# 4_CONN_schdoc.net
KiCad netlist of a schematic drawn in Altium Designer
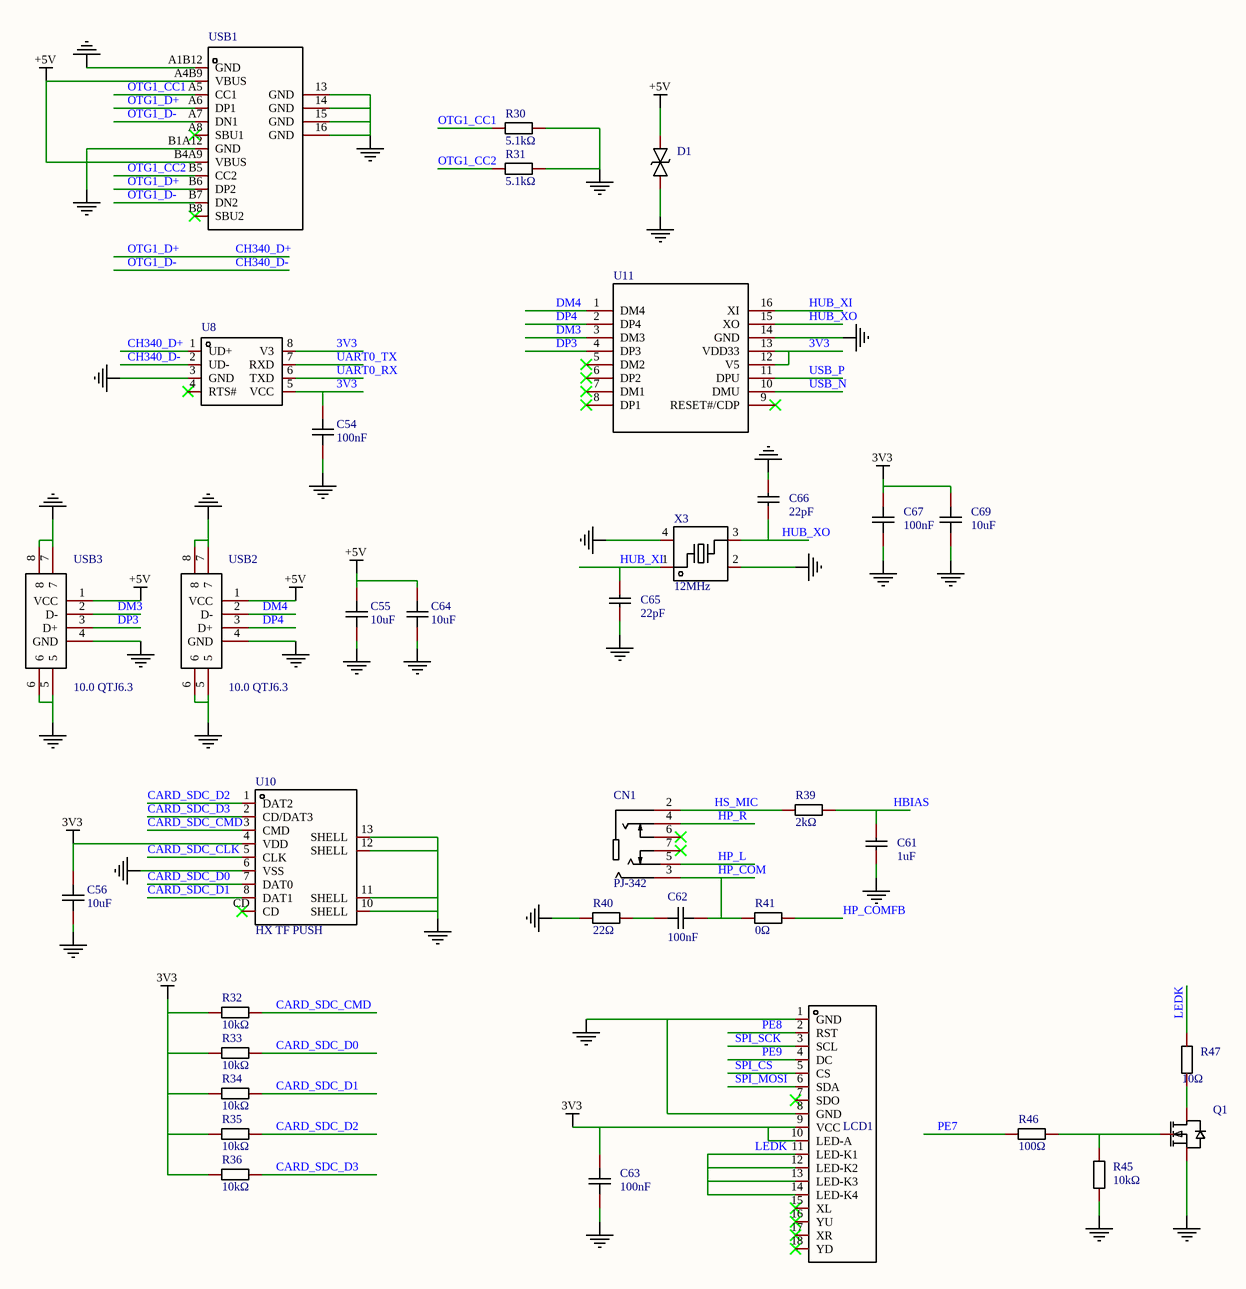
[diagram p0: 4_CONN.schdoc.schdoc]

(export (version "E")
  (design (tool "Eeschema 10.0.6"))
  (components
    (comp (ref "C54")
      (value "100nF")
      (fields
        (field (name "NAME") "100nF")
        (field (name "MANUFACTURER") "YAGEO(国巨)")
        (field (name "MANUFACTURER PART") "CC0603KRX7R9BB104")
        (field (name "TOLERANCE") "±10%")
      )
      (libsource (lib "altium-import") (part "root_1_CC0603KRX7R9BB104_"))
    )
    (comp (ref "C55")
      (value "10uF")
      (fields
        (field (name "NAME") "10uF")
        (field (name "MANUFACTURER") "SAMSUNG(三星)")
        (field (name "MANUFACTURER PART") "CL10A106KP8NNNC")
        (field (name "TOLERANCE") "±10%")
      )
      (libsource (lib "altium-import") (part "root_1_CL10A106KP8NNNC_"))
    )
    (comp (ref "C56")
      (value "10uF")
      (fields
        (field (name "NAME") "10uF")
        (field (name "MANUFACTURER") "SAMSUNG(三星)")
        (field (name "MANUFACTURER PART") "CL10A106KP8NNNC")
        (field (name "TOLERANCE") "±10%")
      )
      (libsource (lib "altium-import") (part "root_1_CL10A106KP8NNNC_"))
    )
    (comp (ref "C61")
      (value "1uF")
      (fields
        (field (name "NAME") "1uF")
        (field (name "MANUFACTURER PART") "CL10A105KB8NNNC")
        (field (name "MANUFACTURER") "SAMSUNG(三星)")
        (field (name "TOLERANCE") "±10%")
      )
      (libsource (lib "altium-import") (part "root_1_CL10A105KB8NNNC_"))
    )
    (comp (ref "C62")
      (value "100nF")
      (fields
        (field (name "NAME") "100nF")
        (field (name "MANUFACTURER") "YAGEO(国巨)")
        (field (name "MANUFACTURER PART") "CC0603KRX7R9BB104")
        (field (name "TOLERANCE") "±10%")
      )
      (libsource (lib "altium-import") (part "root_2_CC0603KRX7R9BB104_"))
    )
    (comp (ref "C63")
      (value "100nF")
      (fields
        (field (name "NAME") "100nF")
        (field (name "MANUFACTURER") "YAGEO(国巨)")
        (field (name "MANUFACTURER PART") "CC0603KRX7R9BB104")
        (field (name "TOLERANCE") "±10%")
      )
      (libsource (lib "altium-import") (part "root_1_CC0603KRX7R9BB104_"))
    )
    (comp (ref "C64")
      (value "10uF")
      (fields
        (field (name "NAME") "10uF")
        (field (name "MANUFACTURER") "SAMSUNG(三星)")
        (field (name "MANUFACTURER PART") "CL10A106KP8NNNC")
        (field (name "TOLERANCE") "±10%")
      )
      (libsource (lib "altium-import") (part "root_1_CL10A106KP8NNNC_"))
    )
    (comp (ref "C65")
      (value "22pF")
      (fields
        (field (name "NAME") "22pF")
        (field (name "MANUFACTURER PART") "CL10C220JB8NNNC")
        (field (name "MANUFACTURER") "SAMSUNG(三星)")
        (field (name "TOLERANCE") "±5%")
      )
      (libsource (lib "altium-import") (part "root_1_CL10C220JB8NNNC_"))
    )
    (comp (ref "C66")
      (value "22pF")
      (fields
        (field (name "NAME") "22pF")
        (field (name "MANUFACTURER PART") "CL10C220JB8NNNC")
        (field (name "MANUFACTURER") "SAMSUNG(三星)")
        (field (name "TOLERANCE") "±5%")
      )
      (libsource (lib "altium-import") (part "root_1_CL10C220JB8NNNC_"))
    )
    (comp (ref "C67")
      (value "100nF")
      (fields
        (field (name "NAME") "100nF")
        (field (name "MANUFACTURER") "YAGEO(国巨)")
        (field (name "MANUFACTURER PART") "CC0603KRX7R9BB104")
        (field (name "TOLERANCE") "±10%")
      )
      (libsource (lib "altium-import") (part "root_1_CC0603KRX7R9BB104_"))
    )
    (comp (ref "C69")
      (value "10uF")
      (fields
        (field (name "NAME") "10uF")
        (field (name "MANUFACTURER") "SAMSUNG(三星)")
        (field (name "MANUFACTURER PART") "CL10A106KP8NNNC")
        (field (name "TOLERANCE") "±10%")
      )
      (libsource (lib "altium-import") (part "root_1_CL10A106KP8NNNC_"))
    )
    (comp (ref "CN1")
      (value "PJ-342")
      (description "连接器类型:3.5mm耳机座;额定电流:500mA;额定电压:30V;工作温度范围:-30℃~+70℃;")
      (fields (field (name "NAME") "PJ-342") (field (name "MANUFACTURER") "SHOU HAN(首韩)"))
      (libsource (lib "altium-import") (part "root_0_PJ-342_C668606_"))
    )
    (comp (ref "D1")
      (value "SMF5.0CA")
      (description "极性:双向;反向截止电压(Vrwm):5V;击穿电压:6.4V;反向漏电流(Ir):800uA;峰值脉冲电流(Ipp)@10/1000μs:21.7A;最大钳位电压:9.2V;")
      (fields (field (name "MANUFACTURER") "AnBon(安邦)"))
      (libsource (lib "altium-import") (part "root_1_SMF5.0CA_C435453_"))
    )
    (comp (ref "LCD1")
      (value "TFT_2.4_18P_SPI_ILI9341_240X320_65K_S_1")
      (description "2.4寸SPI串口液晶屏TFT彩屏ILI9341驱动")
      (libsource (lib "altium-import") (part "root_0_TFT_2.4_18P_SPI_ILI9341_240X320_65K_S_1_"))
    )
    (comp (ref "Q1")
      (value "ao3400_c841146")
      (fields (field (name "MANUFACTURER") "LGE(鲁光)") (field (name "MANUFACTURER PART") "AO3400"))
      (libsource (lib "altium-import") (part "root_0_ao3400_c841146_"))
    )
    (comp (ref "R30")
      (value "5.1kΩ")
      (fields
        (field (name "NAME") "5.1kΩ")
        (field (name "MANUFACTURER") "UNI-ROYAL(厚声)")
        (field (name "MANUFACTURER PART") "0402WGF5101TCE")
        (field (name "TOLERANCE") "±1%")
      )
      (libsource (lib "altium-import") (part "root_0_0402WGF5101TCE_"))
    )
    (comp (ref "R31")
      (value "5.1kΩ")
      (fields
        (field (name "NAME") "5.1kΩ")
        (field (name "MANUFACTURER") "UNI-ROYAL(厚声)")
        (field (name "MANUFACTURER PART") "0402WGF5101TCE")
        (field (name "TOLERANCE") "±1%")
      )
      (libsource (lib "altium-import") (part "root_0_0402WGF5101TCE_"))
    )
    (comp (ref "R32")
      (value "10kΩ")
      (description "电阻类型:厚膜电阻;阻值:10kΩ;精度:±1%;功率:100mW;温度系数:±100ppm/℃;最大工作电压:75V;工作温度范围:-55℃~+155℃;")
      (fields
        (field (name "NAME") "10kΩ")
        (field (name "MANUFACTURER") "UNI-ROYAL(厚声)")
        (field (name "MANUFACTURER PART") "0603WAF1002T5E")
      )
      (libsource (lib "altium-import") (part "root_0_0603WAF1002T5E_"))
    )
    (comp (ref "R33")
      (value "10kΩ")
      (description "电阻类型:厚膜电阻;阻值:10kΩ;精度:±1%;功率:100mW;温度系数:±100ppm/℃;最大工作电压:75V;工作温度范围:-55℃~+155℃;")
      (fields
        (field (name "NAME") "10kΩ")
        (field (name "MANUFACTURER") "UNI-ROYAL(厚声)")
        (field (name "MANUFACTURER PART") "0603WAF1002T5E")
      )
      (libsource (lib "altium-import") (part "root_0_0603WAF1002T5E_"))
    )
    (comp (ref "R34")
      (value "10kΩ")
      (description "电阻类型:厚膜电阻;阻值:10kΩ;精度:±1%;功率:100mW;温度系数:±100ppm/℃;最大工作电压:75V;工作温度范围:-55℃~+155℃;")
      (fields
        (field (name "NAME") "10kΩ")
        (field (name "MANUFACTURER") "UNI-ROYAL(厚声)")
        (field (name "MANUFACTURER PART") "0603WAF1002T5E")
      )
      (libsource (lib "altium-import") (part "root_0_0603WAF1002T5E_"))
    )
    (comp (ref "R35")
      (value "10kΩ")
      (description "电阻类型:厚膜电阻;阻值:10kΩ;精度:±1%;功率:100mW;温度系数:±100ppm/℃;最大工作电压:75V;工作温度范围:-55℃~+155℃;")
      (fields
        (field (name "NAME") "10kΩ")
        (field (name "MANUFACTURER") "UNI-ROYAL(厚声)")
        (field (name "MANUFACTURER PART") "0603WAF1002T5E")
      )
      (libsource (lib "altium-import") (part "root_0_0603WAF1002T5E_"))
    )
    (comp (ref "R36")
      (value "10kΩ")
      (description "电阻类型:厚膜电阻;阻值:10kΩ;精度:±1%;功率:100mW;温度系数:±100ppm/℃;最大工作电压:75V;工作温度范围:-55℃~+155℃;")
      (fields
        (field (name "NAME") "10kΩ")
        (field (name "MANUFACTURER") "UNI-ROYAL(厚声)")
        (field (name "MANUFACTURER PART") "0603WAF1002T5E")
      )
      (libsource (lib "altium-import") (part "root_0_0603WAF1002T5E_"))
    )
    (comp (ref "R39")
      (value "2kΩ")
      (fields
        (field (name "NAME") "2kΩ")
        (field (name "MANUFACTURER") "UNI-ROYAL(厚声)")
        (field (name "MANUFACTURER PART") "0603WAF2001T5E")
        (field (name "TOLERANCE") "±1%")
      )
      (libsource (lib "altium-import") (part "root_0_0603WAF2001T5E_"))
    )
    (comp (ref "R40")
      (value "22Ω")
      (fields
        (field (name "NAME") "22Ω")
        (field (name "MANUFACTURER") "UNI-ROYAL(厚声)")
        (field (name "MANUFACTURER PART") "0603WAF220JT5E")
        (field (name "TOLERANCE") "±1%")
      )
      (libsource (lib "altium-import") (part "root_0_0603WAF220JT5E_"))
    )
    (comp (ref "R41")
      (value "0Ω")
      (fields
        (field (name "NAME") "0Ω")
        (field (name "MANUFACTURER") "UNI-ROYAL(厚声)")
        (field (name "MANUFACTURER PART") "0603WAF0000T5E")
        (field (name "TOLERANCE") "±1%")
      )
      (libsource (lib "altium-import") (part "root_0_0603WAF0000T5E_"))
    )
    (comp (ref "R45")
      (value "10kΩ")
      (fields
        (field (name "NAME") "10kΩ")
        (field (name "MANUFACTURER") "UNI-ROYAL(厚声)")
        (field (name "MANUFACTURER PART") "0603WAF1002T5E")
        (field (name "TOLERANCE") "±1%")
      )
      (libsource (lib "altium-import") (part "root_1_0603WAF1002T5E_"))
    )
    (comp (ref "R46")
      (value "100Ω")
      (fields
        (field (name "NAME") "100Ω")
        (field (name "MANUFACTURER") "UNI-ROYAL(厚声)")
        (field (name "MANUFACTURER PART") "0603WAF1000T5E")
        (field (name "TOLERANCE") "±1%")
      )
      (libsource (lib "altium-import") (part "root_0_0603WAF1000T5E_"))
    )
    (comp (ref "R47")
      (value "10Ω")
      (fields
        (field (name "MANUFACTURER") "UNI-ROYAL(厚声)")
        (field (name "MANUFACTURER PART") "0603WAF100JT5E")
        (field (name "TOLERANCE") "±1%")
      )
      (libsource (lib "altium-import") (part "root_1_0603WAF100JT5E_"))
    )
    (comp (ref "U8")
      (value "CH340N")
      (fields (field (name "MANUFACTURER") "WCH(南京沁恒)"))
      (libsource (lib "altium-import") (part "root_0_CH340N_"))
    )
    (comp (ref "U10")
      (value "HX TF PUSH")
      (fields (field (name "NAME") "HX TF PUSH") (field (name "MANUFACTURER") "hanxia(韩下)"))
      (libsource (lib "altium-import") (part "root_0_HX TF PUSH_"))
    )
    (comp (ref "U11") (value "CH334R") (libsource (lib "altium-import") (part "root_0_CH334R_")))
    (comp (ref "USB1")
      (value "TYPEC-304-BCP16")
      (description "连接器类型:Type-C;标准:USB 3.1;公母:母座;触点数量:16;端口数量:1;安装方式:卧贴;额定电流 - 电源:3A;工作温度范围:-25℃~+85℃;焊接温度(最大值):260℃;")
      (fields (field (name "MANUFACTURER") "XUNPU(讯普)"))
      (libsource (lib "altium-import") (part "root_0_TYPEC-304-BCP16_C720629_"))
    )
    (comp (ref "USB2")
      (value "10.0 QTJ6.3")
      (description "连接器类型:Type-A;标准:USB 2.0;公母:母;触点数量:4P;端口数量:1;安装方式:卧贴;额定电流 - 电源:-;工作温度范围:-;")
      (fields (field (name "NAME") "10.0 QTJ6.3") (field (name "MANUFACTURER") "SHOU HAN(首韩)"))
      (libsource (lib "altium-import") (part "root_1_10.0 QTJ6.3_"))
    )
    (comp (ref "USB3")
      (value "10.0 QTJ6.3")
      (description "连接器类型:Type-A;标准:USB 2.0;公母:母;触点数量:4P;端口数量:1;安装方式:卧贴;额定电流 - 电源:-;工作温度范围:-;")
      (fields (field (name "NAME") "10.0 QTJ6.3") (field (name "MANUFACTURER") "SHOU HAN(首韩)"))
      (libsource (lib "altium-import") (part "root_1_10.0 QTJ6.3_"))
    )
    (comp (ref "X3")
      (value "12MHz")
      (description "频率:12MHz;负载电容:12pF;频率公差:±10ppm;")
      (fields
        (field (name "NAME") "12MHz")
        (field (name "MANUFACTURER") "YXC(扬兴晶振)")
        (field (name "MANUFACTURER PART") "XL2EL89COI-111YLC-12M")
      )
      (libsource (lib "altium-import") (part "root_0_XL2EL89COI-111YLC-12M_"))
    )
  )
  (nets
    (net (code "1") (name "+5V") (class "Default")
      (node (ref "C55") (pin "2") (pinfunction "2_2") (pintype "passive"))
      (node (ref "C64") (pin "2") (pinfunction "2_2") (pintype "passive"))
      (node (ref "D1") (pin "2") (pinfunction "2_2") (pintype "passive"))
      (node (ref "USB1") (pin "A4B9") (pinfunction "VBUS_A4B9") (pintype "passive"))
      (node (ref "USB1") (pin "B4A9") (pinfunction "VBUS_B4A9") (pintype "passive"))
      (node (ref "USB2") (pin "1") (pinfunction "VCC_1") (pintype "passive"))
      (node (ref "USB3") (pin "1") (pinfunction "VCC_1") (pintype "passive"))
    )
    (net (code "2") (name "/CARD_SDC_CLK") (class "Default")
      (node (ref "U10") (pin "5") (pinfunction "CLK_5") (pintype "passive"))
    )
    (net (code "3") (name "/CARD_SDC_CMD") (class "Default")
      (node (ref "R32") (pin "2") (pinfunction "2_2") (pintype "passive"))
      (node (ref "U10") (pin "3") (pinfunction "CMD_3") (pintype "passive"))
    )
    (net (code "4") (name "/CARD_SDC_D0") (class "Default")
      (node (ref "R33") (pin "2") (pinfunction "2_2") (pintype "passive"))
      (node (ref "U10") (pin "7") (pinfunction "DAT0_7") (pintype "passive"))
    )
    (net (code "5") (name "/CARD_SDC_D1") (class "Default")
      (node (ref "R34") (pin "2") (pinfunction "2_2") (pintype "passive"))
      (node (ref "U10") (pin "8") (pinfunction "DAT1_8") (pintype "passive"))
    )
    (net (code "6") (name "/CARD_SDC_D2") (class "Default")
      (node (ref "R35") (pin "2") (pinfunction "2_2") (pintype "passive"))
      (node (ref "U10") (pin "1") (pinfunction "DAT2_1") (pintype "passive"))
    )
    (net (code "7") (name "/CARD_SDC_D3") (class "Default")
      (node (ref "R36") (pin "2") (pinfunction "2_2") (pintype "passive"))
      (node (ref "U10") (pin "2") (pinfunction "CD/DAT3_2") (pintype "passive"))
    )
    (net (code "8") (name "/CH340_D+") (class "Default")
      (node (ref "U8") (pin "1") (pinfunction "UD+_1") (pintype "passive"))
      (node (ref "USB1") (pin "A6") (pinfunction "DP1_A6") (pintype "passive"))
      (node (ref "USB1") (pin "B6") (pinfunction "DP2_B6") (pintype "passive"))
    )
    (net (code "9") (name "/CH340_D-") (class "Default")
      (node (ref "U8") (pin "2") (pinfunction "UD-_2") (pintype "passive"))
      (node (ref "USB1") (pin "A7") (pinfunction "DN1_A7") (pintype "passive"))
      (node (ref "USB1") (pin "B7") (pinfunction "DN2_B7") (pintype "passive"))
    )
    (net (code "10") (name "/DM3") (class "Default")
      (node (ref "U11") (pin "3") (pinfunction "DM3_3") (pintype "passive"))
      (node (ref "USB3") (pin "2") (pinfunction "D-_2") (pintype "passive"))
    )
    (net (code "11") (name "/DM4") (class "Default")
      (node (ref "U11") (pin "1") (pinfunction "DM4_1") (pintype "passive"))
      (node (ref "USB2") (pin "2") (pinfunction "D-_2") (pintype "passive"))
    )
    (net (code "12") (name "/DP3") (class "Default")
      (node (ref "U11") (pin "4") (pinfunction "DP3_4") (pintype "passive"))
      (node (ref "USB3") (pin "3") (pinfunction "D+_3") (pintype "passive"))
    )
    (net (code "13") (name "/DP4") (class "Default")
      (node (ref "U11") (pin "2") (pinfunction "DP4_2") (pintype "passive"))
      (node (ref "USB2") (pin "3") (pinfunction "D+_3") (pintype "passive"))
    )
    (net (code "14") (name "/HBIAS") (class "Default")
      (node (ref "C61") (pin "2") (pinfunction "2_2") (pintype "passive"))
      (node (ref "R39") (pin "2") (pinfunction "2_2") (pintype "passive"))
    )
    (net (code "15") (name "/HP_COM") (class "Default")
      (node (ref "C62") (pin "1") (pinfunction "1_1") (pintype "passive"))
      (node (ref "CN1") (pin "3") (pinfunction "3_3") (pintype "passive"))
      (node (ref "R41") (pin "1") (pinfunction "1_1") (pintype "passive"))
    )
    (net (code "16") (name "/HP_COMFB") (class "Default")
      (node (ref "R41") (pin "2") (pinfunction "2_2") (pintype "passive"))
    )
    (net (code "17") (name "/HP_L") (class "Default")
      (node (ref "CN1") (pin "5") (pinfunction "5_5") (pintype "passive"))
    )
    (net (code "18") (name "/HP_R") (class "Default")
      (node (ref "CN1") (pin "4") (pinfunction "4_4") (pintype "passive"))
    )
    (net (code "19") (name "/HS_MIC") (class "Default")
      (node (ref "CN1") (pin "2") (pinfunction "2_2") (pintype "passive"))
      (node (ref "R39") (pin "1") (pinfunction "1_1") (pintype "passive"))
    )
    (net (code "20") (name "/HUB_XI") (class "Default")
      (node (ref "C65") (pin "2") (pinfunction "2_2") (pintype "passive"))
      (node (ref "U11") (pin "16") (pinfunction "XI_16") (pintype "passive"))
      (node (ref "X3") (pin "1") (pinfunction "1_1") (pintype "passive"))
    )
    (net (code "21") (name "/HUB_XO") (class "Default")
      (node (ref "C66") (pin "1") (pinfunction "1_1") (pintype "passive"))
      (node (ref "U11") (pin "15") (pinfunction "XO_15") (pintype "passive"))
      (node (ref "X3") (pin "3") (pinfunction "3_3") (pintype "passive"))
    )
    (net (code "22") (name "/LEDK") (class "Default")
      (node (ref "LCD1") (pin "11") (pinfunction "LED-K1_11") (pintype "passive"))
      (node (ref "LCD1") (pin "12") (pinfunction "LED-K2_12") (pintype "passive"))
      (node (ref "LCD1") (pin "13") (pinfunction "LED-K3_13") (pintype "passive"))
      (node (ref "LCD1") (pin "14") (pinfunction "LED-K4_14") (pintype "passive"))
      (node (ref "R47") (pin "2") (pinfunction "2_2") (pintype "passive"))
    )
    (net (code "23") (name "/OTG1_CC1") (class "Default")
      (node (ref "R30") (pin "1") (pinfunction "1_1") (pintype "passive"))
      (node (ref "USB1") (pin "A5") (pinfunction "CC1_A5") (pintype "passive"))
    )
    (net (code "24") (name "/OTG1_CC2") (class "Default")
      (node (ref "R31") (pin "1") (pinfunction "1_1") (pintype "passive"))
      (node (ref "USB1") (pin "B5") (pinfunction "CC2_B5") (pintype "passive"))
    )
    (net (code "25") (name "/PE7") (class "Default")
      (node (ref "R46") (pin "1") (pinfunction "1_1") (pintype "passive"))
    )
    (net (code "26") (name "/PE8") (class "Default")
      (node (ref "LCD1") (pin "2") (pinfunction "RST_2") (pintype "passive"))
    )
    (net (code "27") (name "/PE9") (class "Default")
      (node (ref "LCD1") (pin "4") (pinfunction "DC_4") (pintype "passive"))
    )
    (net (code "28") (name "/SPI_CS") (class "Default")
      (node (ref "LCD1") (pin "5") (pinfunction "CS_5") (pintype "passive"))
    )
    (net (code "29") (name "/SPI_MOSI") (class "Default")
      (node (ref "LCD1") (pin "6") (pinfunction "SDA_6") (pintype "passive"))
    )
    (net (code "30") (name "/SPI_SCK") (class "Default")
      (node (ref "LCD1") (pin "3") (pinfunction "SCL_3") (pintype "passive"))
    )
    (net (code "31") (name "/UART0_RX") (class "Default")
      (node (ref "U8") (pin "6") (pinfunction "TXD_6") (pintype "passive"))
    )
    (net (code "32") (name "/UART0_TX") (class "Default")
      (node (ref "U8") (pin "7") (pinfunction "RXD_7") (pintype "passive"))
    )
    (net (code "33") (name "/USB_N") (class "Default")
      (node (ref "U11") (pin "10") (pinfunction "DMU_10") (pintype "passive"))
    )
    (net (code "34") (name "/USB_P") (class "Default")
      (node (ref "U11") (pin "11") (pinfunction "DPU_11") (pintype "passive"))
    )
    (net (code "35") (name "3V3") (class "Default")
      (node (ref "C54") (pin "2") (pinfunction "2_2") (pintype "passive"))
      (node (ref "C56") (pin "2") (pinfunction "2_2") (pintype "passive"))
      (node (ref "C63") (pin "2") (pinfunction "2_2") (pintype "passive"))
      (node (ref "C67") (pin "2") (pinfunction "2_2") (pintype "passive"))
      (node (ref "C69") (pin "2") (pinfunction "2_2") (pintype "passive"))
      (node (ref "LCD1") (pin "10") (pinfunction "LED-A_10") (pintype "passive"))
      (node (ref "LCD1") (pin "9") (pinfunction "VCC_9") (pintype "passive"))
      (node (ref "R32") (pin "1") (pinfunction "1_1") (pintype "passive"))
      (node (ref "R33") (pin "1") (pinfunction "1_1") (pintype "passive"))
      (node (ref "R34") (pin "1") (pinfunction "1_1") (pintype "passive"))
      (node (ref "R35") (pin "1") (pinfunction "1_1") (pintype "passive"))
      (node (ref "R36") (pin "1") (pinfunction "1_1") (pintype "passive"))
      (node (ref "U10") (pin "4") (pinfunction "VDD_4") (pintype "passive"))
      (node (ref "U11") (pin "12") (pinfunction "V5_12") (pintype "passive"))
      (node (ref "U11") (pin "13") (pinfunction "VDD33_13") (pintype "passive"))
      (node (ref "U8") (pin "5") (pinfunction "VCC_5") (pintype "passive"))
      (node (ref "U8") (pin "8") (pinfunction "V3_8") (pintype "passive"))
    )
    (net (code "36") (name "<NO NET>") (class "Default")
      (node (ref "C55") (pin "1") (pinfunction "1_1") (pintype "passive"))
      (node (ref "C56") (pin "1") (pinfunction "1_1") (pintype "passive"))
      (node (ref "C61") (pin "1") (pinfunction "1_1") (pintype "passive"))
      (node (ref "C63") (pin "1") (pinfunction "1_1") (pintype "passive"))
      (node (ref "C64") (pin "1") (pinfunction "1_1") (pintype "passive"))
      (node (ref "C67") (pin "1") (pinfunction "1_1") (pintype "passive"))
      (node (ref "C69") (pin "1") (pinfunction "1_1") (pintype "passive"))
      (node (ref "LCD1") (pin "1") (pinfunction "GND_1") (pintype "passive"))
      (node (ref "LCD1") (pin "8") (pinfunction "GND_8") (pintype "passive"))
      (node (ref "Q1") (pin "2") (pinfunction "S_2") (pintype "passive"))
      (node (ref "R40") (pin "1") (pinfunction "1_1") (pintype "passive"))
      (node (ref "R45") (pin "1") (pinfunction "1_1") (pintype "passive"))
      (node (ref "U10") (pin "10") (pinfunction "SHELL_10") (pintype "passive"))
      (node (ref "U10") (pin "11") (pinfunction "SHELL_11") (pintype "passive"))
      (node (ref "U10") (pin "12") (pinfunction "SHELL_12") (pintype "passive"))
      (node (ref "U10") (pin "13") (pinfunction "SHELL_13") (pintype "passive"))
      (node (ref "U10") (pin "6") (pinfunction "VSS_6") (pintype "passive"))
      (node (ref "U11") (pin "14") (pinfunction "GND_14") (pintype "passive"))
      (node (ref "USB2") (pin "4") (pinfunction "GND_4") (pintype "passive"))
      (node (ref "USB2") (pin "5") (pinfunction "5_5") (pintype "passive"))
      (node (ref "USB2") (pin "6") (pinfunction "6_6") (pintype "passive"))
      (node (ref "USB2") (pin "7") (pinfunction "7_7") (pintype "passive"))
      (node (ref "USB2") (pin "8") (pinfunction "8_8") (pintype "passive"))
      (node (ref "USB3") (pin "4") (pinfunction "GND_4") (pintype "passive"))
      (node (ref "USB3") (pin "5") (pinfunction "5_5") (pintype "passive"))
      (node (ref "USB3") (pin "6") (pinfunction "6_6") (pintype "passive"))
      (node (ref "USB3") (pin "7") (pinfunction "7_7") (pintype "passive"))
      (node (ref "USB3") (pin "8") (pinfunction "8_8") (pintype "passive"))
    )
    (net (code "37") (name "GND") (class "Default")
      (node (ref "C54") (pin "1") (pinfunction "1_1") (pintype "passive"))
      (node (ref "C65") (pin "1") (pinfunction "1_1") (pintype "passive"))
      (node (ref "C66") (pin "2") (pinfunction "2_2") (pintype "passive"))
      (node (ref "D1") (pin "1") (pinfunction "1_1") (pintype "passive"))
      (node (ref "R30") (pin "2") (pinfunction "2_2") (pintype "passive"))
      (node (ref "R31") (pin "2") (pinfunction "2_2") (pintype "passive"))
      (node (ref "U8") (pin "3") (pinfunction "GND_3") (pintype "passive"))
      (node (ref "USB1") (pin "13") (pinfunction "GND_13") (pintype "passive"))
      (node (ref "USB1") (pin "14") (pinfunction "GND_14") (pintype "passive"))
      (node (ref "USB1") (pin "15") (pinfunction "GND_15") (pintype "passive"))
      (node (ref "USB1") (pin "16") (pinfunction "GND_16") (pintype "passive"))
      (node (ref "USB1") (pin "A1B12") (pinfunction "GND_A1B12") (pintype "passive"))
      (node (ref "USB1") (pin "B1A12") (pinfunction "GND_B1A12") (pintype "passive"))
      (node (ref "X3") (pin "2") (pinfunction "GND_2") (pintype "passive"))
      (node (ref "X3") (pin "4") (pinfunction "GND_4") (pintype "passive"))
    )
    (net (code "38") (name "Net-(C62-Pad2)") (class "Default")
      (node (ref "C62") (pin "2") (pinfunction "2_2") (pintype "passive"))
      (node (ref "R40") (pin "2") (pinfunction "2_2") (pintype "passive"))
    )
    (net (code "39") (name "Net-(Q1-D)") (class "Default")
      (node (ref "Q1") (pin "3") (pinfunction "D_3") (pintype "passive"))
      (node (ref "R47") (pin "1") (pinfunction "1_1") (pintype "passive"))
    )
    (net (code "40") (name "Net-(Q1-G)") (class "Default")
      (node (ref "Q1") (pin "1") (pinfunction "G_1") (pintype "passive"))
      (node (ref "R45") (pin "2") (pinfunction "2_2") (pintype "passive"))
      (node (ref "R46") (pin "2") (pinfunction "2_2") (pintype "passive"))
    )
    (net (code "41") (name "unconnected-(CN1-Pad6)") (class "Default")
      (node (ref "CN1") (pin "6") (pinfunction "6_6") (pintype "passive+no_connect"))
    )
    (net (code "42") (name "unconnected-(CN1-Pad7)") (class "Default")
      (node (ref "CN1") (pin "7") (pinfunction "7_7") (pintype "passive+no_connect"))
    )
    (net (code "43") (name "unconnected-(LCD1-SDO-Pad7)") (class "Default")
      (node (ref "LCD1") (pin "7") (pinfunction "SDO_7") (pintype "passive+no_connect"))
    )
    (net (code "44") (name "unconnected-(LCD1-XL-Pad15)") (class "Default")
      (node (ref "LCD1") (pin "15") (pinfunction "XL_15") (pintype "passive+no_connect"))
    )
    (net (code "45") (name "unconnected-(LCD1-XR-Pad17)") (class "Default")
      (node (ref "LCD1") (pin "17") (pinfunction "XR_17") (pintype "passive+no_connect"))
    )
    (net (code "46") (name "unconnected-(LCD1-YD-Pad18)") (class "Default")
      (node (ref "LCD1") (pin "18") (pinfunction "YD_18") (pintype "passive+no_connect"))
    )
    (net (code "47") (name "unconnected-(LCD1-YU-Pad16)") (class "Default")
      (node (ref "LCD1") (pin "16") (pinfunction "YU_16") (pintype "passive+no_connect"))
    )
    (net (code "48") (name "unconnected-(U8-RTS#-Pad4)") (class "Default")
      (node (ref "U8") (pin "4") (pinfunction "RTS#_4") (pintype "passive+no_connect"))
    )
    (net (code "49") (name "unconnected-(U10-PadCD)") (class "Default")
      (node (ref "U10") (pin "CD") (pinfunction "CD_CD") (pintype "passive+no_connect"))
    )
    (net (code "50") (name "unconnected-(U11-DM1-Pad7)") (class "Default")
      (node (ref "U11") (pin "7") (pinfunction "DM1_7") (pintype "passive+no_connect"))
    )
    (net (code "51") (name "unconnected-(U11-DM2-Pad5)") (class "Default")
      (node (ref "U11") (pin "5") (pinfunction "DM2_5") (pintype "passive+no_connect"))
    )
    (net (code "52") (name "unconnected-(U11-DP1-Pad8)") (class "Default")
      (node (ref "U11") (pin "8") (pinfunction "DP1_8") (pintype "passive+no_connect"))
    )
    (net (code "53") (name "unconnected-(U11-DP2-Pad6)") (class "Default")
      (node (ref "U11") (pin "6") (pinfunction "DP2_6") (pintype "passive+no_connect"))
    )
    (net (code "54") (name "unconnected-(U11-RESET#{slash}CDP-Pad9)") (class "Default")
      (node (ref "U11") (pin "9") (pinfunction "RESET#/CDP_9") (pintype "passive+no_connect"))
    )
    (net (code "55") (name "unconnected-(USB1-SBU1-PadA8)") (class "Default")
      (node (ref "USB1") (pin "A8") (pinfunction "SBU1_A8") (pintype "passive+no_connect"))
    )
    (net (code "56") (name "unconnected-(USB1-SBU2-PadB8)") (class "Default")
      (node (ref "USB1") (pin "B8") (pinfunction "SBU2_B8") (pintype "passive+no_connect"))
    )
  )
)
